# CoproMKII_Ethernet.net
KiCad netlist of a schematic drawn in Altium Designer
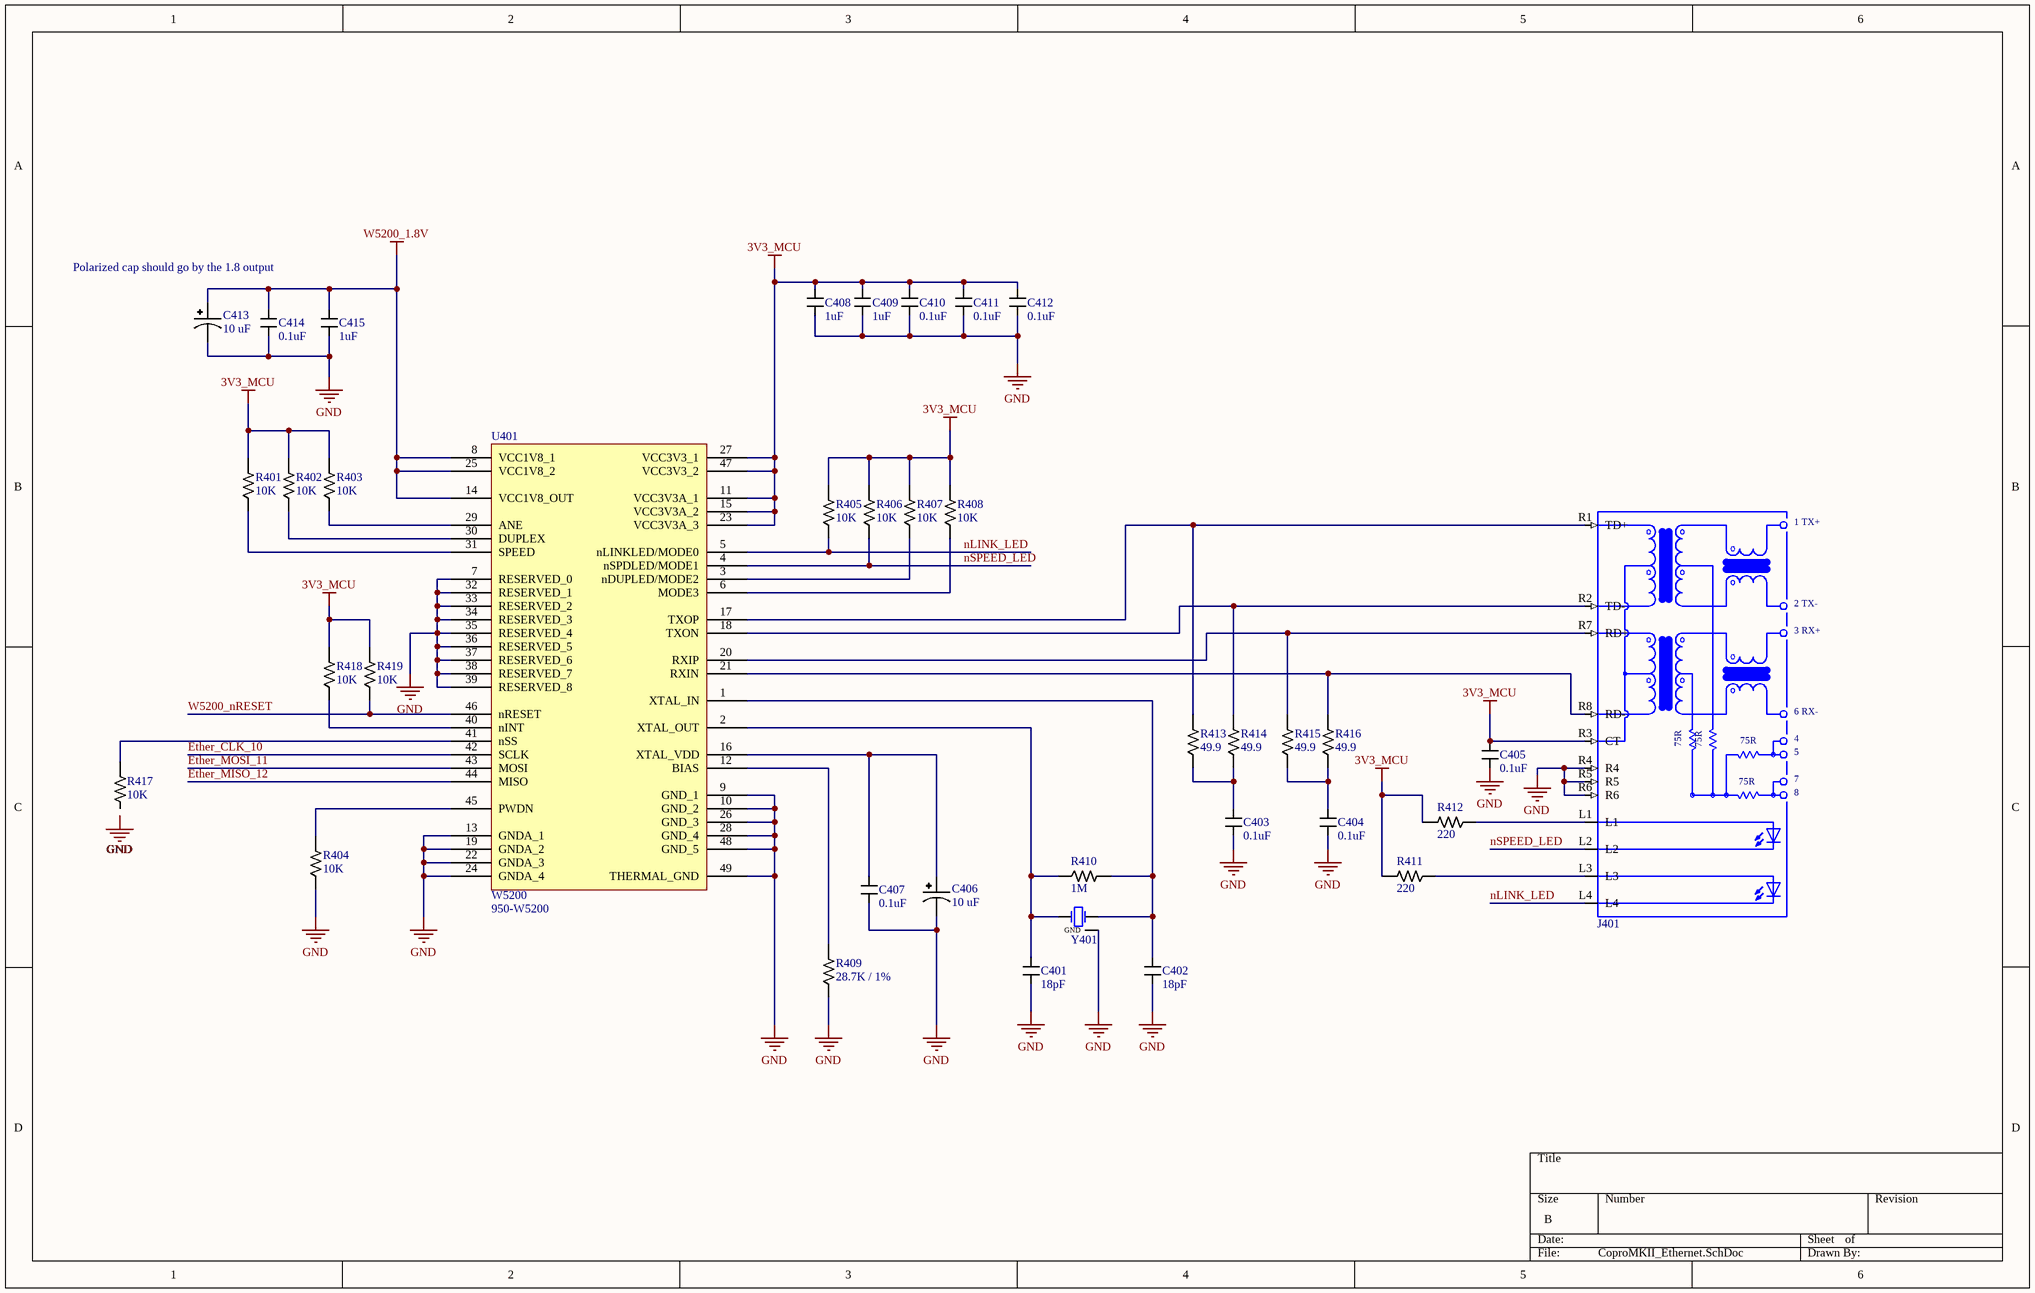
[diagram p0: CoproMKII_Ethernet.SchDoc]

(export (version "E")
  (design (tool "Eeschema 10.0.6"))
  (components
    (comp (ref "C401")
      (value "18pF")
      (footprint "CAPACITOR_0603")
      (description "Cap 18pF 50V +/-5%\r\nCeramic 0603")
      (fields
        (field (name "TOLERANCE") "+/- 5%")
        (field (name "VOLTAGE") "50V")
        (field (name "MADE BY") "Flip B")
      )
      (libsource (lib "Capacitors") (part "CAPACITOR_0.000018uF_0603"))
    )
    (comp (ref "C402")
      (value "18pF")
      (footprint "CAPACITOR_0603")
      (description "Cap 18pF 50V +/-5%\r\nCeramic 0603")
      (fields
        (field (name "TOLERANCE") "+/- 5%")
        (field (name "VOLTAGE") "50V")
        (field (name "MADE BY") "Flip B")
      )
      (libsource (lib "Capacitors") (part "CAPACITOR_0.000018uF_0603"))
    )
    (comp (ref "C403")
      (value "0.1uF")
      (footprint "CAPACITOR_0603")
      (description "Cap 100nF 6.3V +/-10%\r\nCeramic 0603")
      (fields
        (field (name "TOLERANCE") "+/- 10%")
        (field (name "VOLTAGE") "6.3V")
        (field (name "MADE BY") "Flip B")
      )
      (libsource (lib "Capacitors") (part "CAPACITOR_0.1uF_0603"))
    )
    (comp (ref "C404")
      (value "0.1uF")
      (footprint "CAPACITOR_0603")
      (description "Cap 100nF 6.3V +/-10%\r\nCeramic 0603")
      (fields
        (field (name "TOLERANCE") "+/- 10%")
        (field (name "VOLTAGE") "6.3V")
        (field (name "MADE BY") "Flip B")
      )
      (libsource (lib "Capacitors") (part "CAPACITOR_0.1uF_0603"))
    )
    (comp (ref "C405")
      (value "0.1uF")
      (footprint "CAPACITOR_0603")
      (description "Cap 100nF 6.3V +/-10%\r\nCeramic 0603")
      (fields
        (field (name "TOLERANCE") "+/- 10%")
        (field (name "VOLTAGE") "6.3V")
        (field (name "MADE BY") "Flip B")
      )
      (libsource (lib "Capacitors") (part "CAPACITOR_0.1uF_0603"))
    )
    (comp (ref "C406")
      (value "10uF Tantalum 10V")
      (footprint "CAPACITOR_0603")
      (description "Cap 10uF 10V +/-20%\r\nTantalum 0603")
      (fields
        (field (name "TOLERANCE") "+/- 20%")
        (field (name "VOLTAGE") "10V")
        (field (name "VALUE (UF)") "10 uF")
        (field (name "MADE BY") "John S")
      )
      (libsource (lib "Capacitors") (part "CAPACITOR_10uF_0603_Tantalum"))
    )
    (comp (ref "C407")
      (value "0.1uF")
      (footprint "CAPACITOR_0603")
      (description "Cap 100nF 6.3V +/-10%\r\nCeramic 0603")
      (fields
        (field (name "TOLERANCE") "+/- 10%")
        (field (name "VOLTAGE") "6.3V")
        (field (name "MADE BY") "Flip B")
      )
      (libsource (lib "Capacitors") (part "CAPACITOR_0.1uF_0603"))
    )
    (comp (ref "C408")
      (value "1uF")
      (footprint "CAPACITOR_0603")
      (description "Cap 1uF 16V +/-10%\r\nCeramic 0603")
      (fields
        (field (name "TOLERANCE") "+/- 10%")
        (field (name "VOLTAGE") "16V")
        (field (name "MADE BY") "Flip B")
      )
      (libsource (lib "Capacitors") (part "CAPACITOR_1uF_0603"))
    )
    (comp (ref "C409")
      (value "1uF")
      (footprint "CAPACITOR_0603")
      (description "Cap 1uF 16V +/-10%\r\nCeramic 0603")
      (fields
        (field (name "TOLERANCE") "+/- 10%")
        (field (name "VOLTAGE") "16V")
        (field (name "MADE BY") "Flip B")
      )
      (libsource (lib "Capacitors") (part "CAPACITOR_1uF_0603"))
    )
    (comp (ref "C410")
      (value "0.1uF")
      (footprint "CAPACITOR_0603")
      (description "Cap 100nF 6.3V +/-10%\r\nCeramic 0603")
      (fields
        (field (name "TOLERANCE") "+/- 10%")
        (field (name "VOLTAGE") "6.3V")
        (field (name "MADE BY") "Flip B")
      )
      (libsource (lib "Capacitors") (part "CAPACITOR_0.1uF_0603"))
    )
    (comp (ref "C411")
      (value "0.1uF")
      (footprint "CAPACITOR_0603")
      (description "Cap 100nF 6.3V +/-10%\r\nCeramic 0603")
      (fields
        (field (name "TOLERANCE") "+/- 10%")
        (field (name "VOLTAGE") "6.3V")
        (field (name "MADE BY") "Flip B")
      )
      (libsource (lib "Capacitors") (part "CAPACITOR_0.1uF_0603"))
    )
    (comp (ref "C412")
      (value "0.1uF")
      (footprint "CAPACITOR_0603")
      (description "Cap 100nF 6.3V +/-10%\r\nCeramic 0603")
      (fields
        (field (name "TOLERANCE") "+/- 10%")
        (field (name "VOLTAGE") "6.3V")
        (field (name "MADE BY") "Flip B")
      )
      (libsource (lib "Capacitors") (part "CAPACITOR_0.1uF_0603"))
    )
    (comp (ref "C413")
      (value "10uF Tantalum 10V")
      (footprint "CAPACITOR_0603")
      (description "Cap 10uF 10V +/-20%\r\nTantalum 0603")
      (fields
        (field (name "TOLERANCE") "+/- 20%")
        (field (name "VOLTAGE") "10V")
        (field (name "VALUE (UF)") "10 uF")
        (field (name "MADE BY") "John S")
      )
      (libsource (lib "Capacitors") (part "CAPACITOR_10uF_0603_Tantalum"))
    )
    (comp (ref "C414")
      (value "0.1uF")
      (footprint "CAPACITOR_0603")
      (description "Cap 100nF 6.3V +/-10%\r\nCeramic 0603")
      (fields
        (field (name "TOLERANCE") "+/- 10%")
        (field (name "VOLTAGE") "6.3V")
        (field (name "MADE BY") "Flip B")
      )
      (libsource (lib "Capacitors") (part "CAPACITOR_0.1uF_0603"))
    )
    (comp (ref "C415")
      (value "1uF")
      (footprint "CAPACITOR_0603")
      (description "Cap 1uF 16V +/-10%\r\nCeramic 0603")
      (fields
        (field (name "TOLERANCE") "+/- 10%")
        (field (name "VOLTAGE") "16V")
        (field (name "MADE BY") "Flip B")
      )
      (libsource (lib "Capacitors") (part "CAPACITOR_1uF_0603"))
    )
    (comp (ref "J401")
      (value "Ethernet Connector")
      (footprint "WIZNET_RB1-125BAG1A")
      (description "CONN JACK 1PORT 100 BASE-T PCB")
      (libsource (lib "Connectors") (part "RB1-125BAG1A"))
    )
    (comp (ref "R401")
      (value "10k Ohm 5% 1/10W")
      (footprint "RESISTOR_0603")
      (description "RES 10k OHM 5% 1/10W 0603")
      (fields
        (field (name "TOLERANCE") "+/- 5%")
        (field (name "VALUE  (OHMS)") "10K")
        (field (name "MADE BY") "Robert Pafford")
      )
      (libsource (lib "Resistors") (part "RESISTOR_10K_0603"))
    )
    (comp (ref "R402")
      (value "10k Ohm 5% 1/10W")
      (footprint "RESISTOR_0603")
      (description "RES 10k OHM 5% 1/10W 0603")
      (fields
        (field (name "TOLERANCE") "+/- 5%")
        (field (name "VALUE  (OHMS)") "10K")
        (field (name "MADE BY") "Robert Pafford")
      )
      (libsource (lib "Resistors") (part "RESISTOR_10K_0603"))
    )
    (comp (ref "R403")
      (value "10k Ohm 5% 1/10W")
      (footprint "RESISTOR_0603")
      (description "RES 10k OHM 5% 1/10W 0603")
      (fields
        (field (name "TOLERANCE") "+/- 5%")
        (field (name "VALUE  (OHMS)") "10K")
        (field (name "MADE BY") "Robert Pafford")
      )
      (libsource (lib "Resistors") (part "RESISTOR_10K_0603"))
    )
    (comp (ref "R404")
      (value "10k Ohm 5% 1/10W")
      (footprint "RESISTOR_0603")
      (description "RES 10k OHM 5% 1/10W 0603")
      (fields
        (field (name "TOLERANCE") "+/- 5%")
        (field (name "VALUE  (OHMS)") "10K")
        (field (name "MADE BY") "Robert Pafford")
      )
      (libsource (lib "Resistors") (part "RESISTOR_10K_0603"))
    )
    (comp (ref "R405")
      (value "10k Ohm 5% 1/10W")
      (footprint "RESISTOR_0603")
      (description "RES 10k OHM 5% 1/10W 0603")
      (fields
        (field (name "TOLERANCE") "+/- 5%")
        (field (name "VALUE  (OHMS)") "10K")
        (field (name "MADE BY") "Robert Pafford")
      )
      (libsource (lib "Resistors") (part "RESISTOR_10K_0603"))
    )
    (comp (ref "R406")
      (value "10k Ohm 5% 1/10W")
      (footprint "RESISTOR_0603")
      (description "RES 10k OHM 5% 1/10W 0603")
      (fields
        (field (name "TOLERANCE") "+/- 5%")
        (field (name "VALUE  (OHMS)") "10K")
        (field (name "MADE BY") "Robert Pafford")
      )
      (libsource (lib "Resistors") (part "RESISTOR_10K_0603"))
    )
    (comp (ref "R407")
      (value "10k Ohm 5% 1/10W")
      (footprint "RESISTOR_0603")
      (description "RES 10k OHM 5% 1/10W 0603")
      (fields
        (field (name "TOLERANCE") "+/- 5%")
        (field (name "VALUE  (OHMS)") "10K")
        (field (name "MADE BY") "Robert Pafford")
      )
      (libsource (lib "Resistors") (part "RESISTOR_10K_0603"))
    )
    (comp (ref "R408")
      (value "10k Ohm 5% 1/10W")
      (footprint "RESISTOR_0603")
      (description "RES 10k OHM 5% 1/10W 0603")
      (fields
        (field (name "TOLERANCE") "+/- 5%")
        (field (name "VALUE  (OHMS)") "10K")
        (field (name "MADE BY") "Robert Pafford")
      )
      (libsource (lib "Resistors") (part "RESISTOR_10K_0603"))
    )
    (comp (ref "R409")
      (value "K / 1%")
      (footprint "RESISTOR_0603")
      (description "RES 28.7K OHM 1% 1/8W 0603")
      (fields
        (field (name "TOLERANCE") "+/- 5%")
        (field (name "VALUE  (OHMS)") "28.7K / 1%")
        (field (name "MADE BY") "Robert Pafford")
      )
      (libsource (lib "Resistors") (part "RESISTOR_28.7K / 1%_0603"))
    )
    (comp (ref "R410")
      (value "1M")
      (footprint "RESISTOR_0603")
      (description "RES 1M OHM 1/8W 0603")
      (fields
        (field (name "TOLERANCE") "+/- 5%")
        (field (name "VALUE  (OHMS)") "1M")
        (field (name "MADE BY") "Robert Pafford")
      )
      (libsource (lib "Resistors") (part "RESISTOR_1M_0603"))
    )
    (comp (ref "R411")
      (value "220 Ohm 5% 1/8W")
      (footprint "RESISTOR_0603")
      (description "RES 220 OHM 5% 1/8W 0603")
      (fields
        (field (name "TOLERANCE") "+/- 5%")
        (field (name "VALUE  (OHMS)") "220")
        (field (name "MADE BY") "John S")
      )
      (libsource (lib "Resistors") (part "RESISTOR_200_0603"))
    )
    (comp (ref "R412")
      (value "220 Ohm 5% 1/8W")
      (footprint "RESISTOR_0603")
      (description "RES 220 OHM 5% 1/8W 0603")
      (fields
        (field (name "TOLERANCE") "+/- 5%")
        (field (name "VALUE  (OHMS)") "220")
        (field (name "MADE BY") "John S")
      )
      (libsource (lib "Resistors") (part "RESISTOR_200_0603"))
    )
    (comp (ref "R413")
      (value "49.9 Ohm 1% 1/8W")
      (footprint "RESISTOR_0603")
      (description "RES 49.9 OHM 1% 1/8W 0603")
      (fields
        (field (name "TOLERANCE") "+/- 1%")
        (field (name "VALUE  (OHMS)") "49.9")
        (field (name "MADE BY") "John S")
      )
      (libsource (lib "Resistors") (part "RESISTOR_49.9_0603"))
    )
    (comp (ref "R414")
      (value "49.9 Ohm 1% 1/8W")
      (footprint "RESISTOR_0603")
      (description "RES 49.9 OHM 1% 1/8W 0603")
      (fields
        (field (name "TOLERANCE") "+/- 1%")
        (field (name "VALUE  (OHMS)") "49.9")
        (field (name "MADE BY") "John S")
      )
      (libsource (lib "Resistors") (part "RESISTOR_49.9_0603"))
    )
    (comp (ref "R415")
      (value "49.9 Ohm 1% 1/8W")
      (footprint "RESISTOR_0603")
      (description "RES 49.9 OHM 1% 1/8W 0603")
      (fields
        (field (name "TOLERANCE") "+/- 1%")
        (field (name "VALUE  (OHMS)") "49.9")
        (field (name "MADE BY") "John S")
      )
      (libsource (lib "Resistors") (part "RESISTOR_49.9_0603"))
    )
    (comp (ref "R416")
      (value "49.9 Ohm 1% 1/8W")
      (footprint "RESISTOR_0603")
      (description "RES 49.9 OHM 1% 1/8W 0603")
      (fields
        (field (name "TOLERANCE") "+/- 1%")
        (field (name "VALUE  (OHMS)") "49.9")
        (field (name "MADE BY") "John S")
      )
      (libsource (lib "Resistors") (part "RESISTOR_49.9_0603"))
    )
    (comp (ref "R417")
      (value "10k Ohm 5% 1/10W")
      (footprint "RESISTOR_0603")
      (description "RES 10k OHM 5% 1/10W 0603")
      (fields
        (field (name "TOLERANCE") "+/- 5%")
        (field (name "VALUE  (OHMS)") "10K")
        (field (name "MADE BY") "Robert Pafford")
      )
      (libsource (lib "Resistors") (part "RESISTOR_10K_0603"))
    )
    (comp (ref "R418")
      (value "10k Ohm 5% 1/10W")
      (footprint "RESISTOR_0603")
      (description "RES 10k OHM 5% 1/10W 0603")
      (fields
        (field (name "TOLERANCE") "+/- 5%")
        (field (name "VALUE  (OHMS)") "10K")
        (field (name "MADE BY") "Robert Pafford")
      )
      (libsource (lib "Resistors") (part "RESISTOR_10K_0603"))
    )
    (comp (ref "R419")
      (value "10k Ohm 5% 1/10W")
      (footprint "RESISTOR_0603")
      (description "RES 10k OHM 5% 1/10W 0603")
      (fields
        (field (name "TOLERANCE") "+/- 5%")
        (field (name "VALUE  (OHMS)") "10K")
        (field (name "MADE BY") "Robert Pafford")
      )
      (libsource (lib "Resistors") (part "RESISTOR_10K_0603"))
    )
    (comp (ref "U401")
      (value "W5200")
      (footprint "QFN-48")
      (description "WIZNET W5200\r\n48QFN (7x7 mm)")
      (fields
        (field (name "MF") "Texas Instruments")
        (field (name "MP") "LM1117IMPX-3.3/NOPB")
        (field (name "SUPPLIER PART NUMBER 1") "950-W5200")
        (field (name "CREATED BY:") "Siddharth.V")
      )
      (libsource (lib "Integrated Circuits") (part "W5200"))
    )
    (comp (ref "Y401")
      (value "CRYSTAL 12.0000MHZ 18PF SMD")
      (footprint "4-SMD No Lead Crystal")
      (description "25 MHz ±20ppm Crystal 18pF")
      (fields (field (name "MADE BY") "Robert Pafford"))
      (libsource (lib "Crystals") (part "CRYSTAL_25MHz_SMD_1"))
    )
  )
  (nets
    (net (code "1") (name "/Ether_CLK_10") (class "Default")
      (node (ref "U401") (pin "42") (pinfunction "SCLK_42") (pintype "passive"))
    )
    (net (code "2") (name "/Ether_MISO_12") (class "Default")
      (node (ref "U401") (pin "44") (pinfunction "MISO_44") (pintype "passive"))
    )
    (net (code "3") (name "/Ether_MOSI_11") (class "Default")
      (node (ref "U401") (pin "43") (pinfunction "MOSI_43") (pintype "passive"))
    )
    (net (code "4") (name "/W5200_nRESET") (class "Default")
      (node (ref "R419") (pin "2") (pinfunction "2_2") (pintype "passive"))
      (node (ref "U401") (pin "46") (pinfunction "nRESET_46") (pintype "passive"))
    )
    (net (code "5") (name "/nLINK_LED") (class "Default")
      (node (ref "J401") (pin "L4") (pinfunction "L4_L4") (pintype "passive"))
      (node (ref "R405") (pin "2") (pinfunction "2_2") (pintype "passive"))
      (node (ref "U401") (pin "5") (pinfunction "nLINKLED/MODE0_5") (pintype "passive"))
    )
    (net (code "6") (name "/nSPEED_LED") (class "Default")
      (node (ref "J401") (pin "L2") (pinfunction "L2_L2") (pintype "passive"))
      (node (ref "R406") (pin "2") (pinfunction "2_2") (pintype "passive"))
      (node (ref "U401") (pin "4") (pinfunction "nSPDLED/MODE1_4") (pintype "passive"))
    )
    (net (code "7") (name "3V3_MCU") (class "Default")
      (node (ref "C405") (pin "1") (pinfunction "1_1") (pintype "passive"))
      (node (ref "C408") (pin "1") (pinfunction "1_1") (pintype "passive"))
      (node (ref "C409") (pin "1") (pinfunction "1_1") (pintype "passive"))
      (node (ref "C410") (pin "1") (pinfunction "1_1") (pintype "passive"))
      (node (ref "C411") (pin "1") (pinfunction "1_1") (pintype "passive"))
      (node (ref "C412") (pin "1") (pinfunction "1_1") (pintype "passive"))
      (node (ref "J401") (pin "R3") (pinfunction "CT_R3") (pintype "input"))
      (node (ref "R401") (pin "1") (pinfunction "1_1") (pintype "passive"))
      (node (ref "R402") (pin "1") (pinfunction "1_1") (pintype "passive"))
      (node (ref "R403") (pin "1") (pinfunction "1_1") (pintype "passive"))
      (node (ref "R405") (pin "1") (pinfunction "1_1") (pintype "passive"))
      (node (ref "R406") (pin "1") (pinfunction "1_1") (pintype "passive"))
      (node (ref "R407") (pin "1") (pinfunction "1_1") (pintype "passive"))
      (node (ref "R408") (pin "1") (pinfunction "1_1") (pintype "passive"))
      (node (ref "R411") (pin "1") (pinfunction "1_1") (pintype "passive"))
      (node (ref "R412") (pin "1") (pinfunction "1_1") (pintype "passive"))
      (node (ref "R418") (pin "1") (pinfunction "1_1") (pintype "passive"))
      (node (ref "R419") (pin "1") (pinfunction "1_1") (pintype "passive"))
      (node (ref "U401") (pin "11") (pinfunction "VCC3V3A_1_11") (pintype "passive"))
      (node (ref "U401") (pin "15") (pinfunction "VCC3V3A_2_15") (pintype "passive"))
      (node (ref "U401") (pin "23") (pinfunction "VCC3V3A_3_23") (pintype "passive"))
      (node (ref "U401") (pin "27") (pinfunction "VCC3V3_1_27") (pintype "passive"))
      (node (ref "U401") (pin "47") (pinfunction "VCC3V3_2_47") (pintype "passive"))
    )
    (net (code "8") (name "GND") (class "Default")
      (node (ref "C401") (pin "2") (pinfunction "2_2") (pintype "passive"))
      (node (ref "C402") (pin "2") (pinfunction "2_2") (pintype "passive"))
      (node (ref "C403") (pin "2") (pinfunction "2_2") (pintype "passive"))
      (node (ref "C404") (pin "2") (pinfunction "2_2") (pintype "passive"))
      (node (ref "C405") (pin "2") (pinfunction "2_2") (pintype "passive"))
      (node (ref "C406") (pin "2") (pintype "passive"))
      (node (ref "C407") (pin "2") (pinfunction "2_2") (pintype "passive"))
      (node (ref "C408") (pin "2") (pinfunction "2_2") (pintype "passive"))
      (node (ref "C409") (pin "2") (pinfunction "2_2") (pintype "passive"))
      (node (ref "C410") (pin "2") (pinfunction "2_2") (pintype "passive"))
      (node (ref "C411") (pin "2") (pinfunction "2_2") (pintype "passive"))
      (node (ref "C412") (pin "2") (pinfunction "2_2") (pintype "passive"))
      (node (ref "C413") (pin "2") (pintype "passive"))
      (node (ref "C414") (pin "2") (pinfunction "2_2") (pintype "passive"))
      (node (ref "C415") (pin "2") (pinfunction "2_2") (pintype "passive"))
      (node (ref "J401") (pin "R4") (pinfunction "R4_R4") (pintype "input"))
      (node (ref "J401") (pin "R5") (pinfunction "R5_R5") (pintype "input"))
      (node (ref "J401") (pin "R6") (pinfunction "R6_R6") (pintype "input"))
      (node (ref "R404") (pin "2") (pinfunction "2_2") (pintype "passive"))
      (node (ref "R409") (pin "2") (pinfunction "2_2") (pintype "passive"))
      (node (ref "U401") (pin "10") (pinfunction "GND_2_10") (pintype "passive"))
      (node (ref "U401") (pin "13") (pinfunction "GNDA_1_13") (pintype "passive"))
      (node (ref "U401") (pin "19") (pinfunction "GNDA_2_19") (pintype "passive"))
      (node (ref "U401") (pin "22") (pinfunction "GNDA_3_22") (pintype "passive"))
      (node (ref "U401") (pin "24") (pinfunction "GNDA_4_24") (pintype "passive"))
      (node (ref "U401") (pin "26") (pinfunction "GND_3_26") (pintype "passive"))
      (node (ref "U401") (pin "28") (pinfunction "GND_4_28") (pintype "passive"))
      (node (ref "U401") (pin "32") (pinfunction "RESERVED_1_32") (pintype "passive"))
      (node (ref "U401") (pin "33") (pinfunction "RESERVED_2_33") (pintype "passive"))
      (node (ref "U401") (pin "34") (pinfunction "RESERVED_3_34") (pintype "passive"))
      (node (ref "U401") (pin "35") (pinfunction "RESERVED_4_35") (pintype "passive"))
      (node (ref "U401") (pin "36") (pinfunction "RESERVED_5_36") (pintype "passive"))
      (node (ref "U401") (pin "37") (pinfunction "RESERVED_6_37") (pintype "passive"))
      (node (ref "U401") (pin "38") (pinfunction "RESERVED_7_38") (pintype "passive"))
      (node (ref "U401") (pin "39") (pinfunction "RESERVED_8_39") (pintype "passive"))
      (node (ref "U401") (pin "48") (pinfunction "GND_5_48") (pintype "passive"))
      (node (ref "U401") (pin "49") (pinfunction "THERMAL_GND_49") (pintype "passive"))
      (node (ref "U401") (pin "7") (pinfunction "RESERVED_0_7") (pintype "passive"))
      (node (ref "U401") (pin "9") (pinfunction "GND_1_9") (pintype "passive"))
      (node (ref "Y401") (pin "GND") (pinfunction "GND_GND") (pintype "power_in"))
    )
    (net (code "9") (name "Net-(C403-Pad1)") (class "Default")
      (node (ref "C403") (pin "1") (pinfunction "1_1") (pintype "passive"))
      (node (ref "R413") (pin "2") (pinfunction "2_2") (pintype "passive"))
      (node (ref "R414") (pin "2") (pinfunction "2_2") (pintype "passive"))
    )
    (net (code "10") (name "Net-(C404-Pad1)") (class "Default")
      (node (ref "C404") (pin "1") (pinfunction "1_1") (pintype "passive"))
      (node (ref "R415") (pin "2") (pinfunction "2_2") (pintype "passive"))
      (node (ref "R416") (pin "2") (pinfunction "2_2") (pintype "passive"))
    )
    (net (code "11") (name "Net-(J401-PadL1)") (class "Default")
      (node (ref "J401") (pin "L1") (pinfunction "L1_L1") (pintype "passive"))
      (node (ref "R412") (pin "2") (pinfunction "2_2") (pintype "passive"))
    )
    (net (code "12") (name "Net-(J401-PadL3)") (class "Default")
      (node (ref "J401") (pin "L3") (pinfunction "L3_L3") (pintype "passive"))
      (node (ref "R411") (pin "2") (pinfunction "2_2") (pintype "passive"))
    )
    (net (code "13") (name "Net-(J401-RD+)") (class "Default")
      (node (ref "J401") (pin "R7") (pinfunction "RD+_R7") (pintype "input"))
      (node (ref "R415") (pin "1") (pinfunction "1_1") (pintype "passive"))
      (node (ref "U401") (pin "20") (pinfunction "RXIP_20") (pintype "passive"))
    )
    (net (code "14") (name "Net-(J401-RD-)") (class "Default")
      (node (ref "J401") (pin "R8") (pinfunction "RD-_R8") (pintype "input"))
      (node (ref "R416") (pin "1") (pinfunction "1_1") (pintype "passive"))
      (node (ref "U401") (pin "21") (pinfunction "RXIN_21") (pintype "passive"))
    )
    (net (code "15") (name "Net-(J401-TD+)") (class "Default")
      (node (ref "J401") (pin "R1") (pinfunction "TD+_R1") (pintype "input"))
      (node (ref "R413") (pin "1") (pinfunction "1_1") (pintype "passive"))
      (node (ref "U401") (pin "17") (pinfunction "TXOP_17") (pintype "passive"))
    )
    (net (code "16") (name "Net-(J401-TD-)") (class "Default")
      (node (ref "J401") (pin "R2") (pinfunction "TD-_R2") (pintype "input"))
      (node (ref "R414") (pin "1") (pinfunction "1_1") (pintype "passive"))
      (node (ref "U401") (pin "18") (pinfunction "TXON_18") (pintype "passive"))
    )
    (net (code "17") (name "Net-(U401-ANE)") (class "Default")
      (node (ref "R403") (pin "2") (pinfunction "2_2") (pintype "passive"))
      (node (ref "U401") (pin "29") (pinfunction "ANE_29") (pintype "passive"))
    )
    (net (code "18") (name "Net-(U401-BIAS)") (class "Default")
      (node (ref "R409") (pin "1") (pinfunction "1_1") (pintype "passive"))
      (node (ref "U401") (pin "12") (pinfunction "BIAS_12") (pintype "passive"))
    )
    (net (code "19") (name "Net-(U401-DUPLEX)") (class "Default")
      (node (ref "R402") (pin "2") (pinfunction "2_2") (pintype "passive"))
      (node (ref "U401") (pin "30") (pinfunction "DUPLEX_30") (pintype "passive"))
    )
    (net (code "20") (name "Net-(U401-MODE3)") (class "Default")
      (node (ref "R408") (pin "2") (pinfunction "2_2") (pintype "passive"))
      (node (ref "U401") (pin "6") (pinfunction "MODE3_6") (pintype "passive"))
    )
    (net (code "21") (name "Net-(U401-PWDN)") (class "Default")
      (node (ref "R404") (pin "1") (pinfunction "1_1") (pintype "passive"))
      (node (ref "U401") (pin "45") (pinfunction "PWDN_45") (pintype "passive"))
    )
    (net (code "22") (name "Net-(U401-SPEED)") (class "Default")
      (node (ref "R401") (pin "2") (pinfunction "2_2") (pintype "passive"))
      (node (ref "U401") (pin "31") (pinfunction "SPEED_31") (pintype "passive"))
    )
    (net (code "23") (name "Net-(U401-XTAL_IN)") (class "Default")
      (node (ref "C402") (pin "1") (pinfunction "1_1") (pintype "passive"))
      (node (ref "R410") (pin "1") (pinfunction "1_1") (pintype "passive"))
      (node (ref "U401") (pin "1") (pinfunction "XTAL_IN_1") (pintype "passive"))
      (node (ref "Y401") (pin "2") (pinfunction "2_2") (pintype "passive"))
    )
    (net (code "24") (name "Net-(U401-XTAL_OUT)") (class "Default")
      (node (ref "C401") (pin "1") (pinfunction "1_1") (pintype "passive"))
      (node (ref "R410") (pin "2") (pinfunction "2_2") (pintype "passive"))
      (node (ref "U401") (pin "2") (pinfunction "XTAL_OUT_2") (pintype "passive"))
      (node (ref "Y401") (pin "1") (pinfunction "1_1") (pintype "passive"))
    )
    (net (code "25") (name "Net-(U401-XTAL_VDD)") (class "Default")
      (node (ref "C406") (pin "1") (pintype "passive"))
      (node (ref "C407") (pin "1") (pinfunction "1_1") (pintype "passive"))
      (node (ref "U401") (pin "16") (pinfunction "XTAL_VDD_16") (pintype "passive"))
    )
    (net (code "26") (name "Net-(U401-nDUPLED{slash}MODE2)") (class "Default")
      (node (ref "R407") (pin "2") (pinfunction "2_2") (pintype "passive"))
      (node (ref "U401") (pin "3") (pinfunction "nDUPLED/MODE2_3") (pintype "passive"))
    )
    (net (code "27") (name "Net-(U401-nINT)") (class "Default")
      (node (ref "R418") (pin "2") (pinfunction "2_2") (pintype "passive"))
      (node (ref "U401") (pin "40") (pinfunction "nINT_40") (pintype "passive"))
    )
    (net (code "28") (name "Net-(U401-nSS)") (class "Default")
      (node (ref "R417") (pin "1") (pinfunction "1_1") (pintype "passive"))
      (node (ref "U401") (pin "41") (pinfunction "nSS_41") (pintype "passive"))
    )
    (net (code "29") (name "W5200_1.8V") (class "Default")
      (node (ref "C413") (pin "1") (pintype "passive"))
      (node (ref "C414") (pin "1") (pinfunction "1_1") (pintype "passive"))
      (node (ref "C415") (pin "1") (pinfunction "1_1") (pintype "passive"))
      (node (ref "U401") (pin "14") (pinfunction "VCC1V8_OUT_14") (pintype "passive"))
      (node (ref "U401") (pin "25") (pinfunction "VCC1V8_2_25") (pintype "passive"))
      (node (ref "U401") (pin "8") (pinfunction "VCC1V8_1_8") (pintype "passive"))
    )
    (net (code "30") (name "unconnected-(R417-Pad2)") (class "Default")
      (node (ref "R417") (pin "2") (pinfunction "2_2") (pintype "passive"))
    )
  )
)
